# Mircod_TEST_LIST_2.net
KiCad netlist of a schematic drawn in Altium Designer
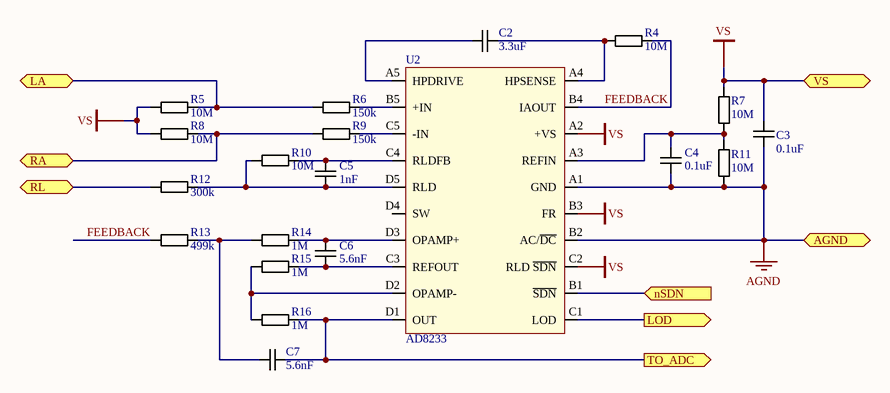
[diagram p0: Mircod_TEST_LIST_2.SchDoc]

(export (version "E")
  (design (tool "Eeschema 10.0.6"))
  (components
    (comp (ref "C2")
      (value "3.3uF")
      (footprint "MIRCOD:Csmd_0402")
      (description "CAPACITOR")
      (libsource (lib "MIRCOD") (part "C_SMD"))
    )
    (comp (ref "C3")
      (value "0.1uF")
      (footprint "MIRCOD:Csmd_0402")
      (description "CAPACITOR")
      (libsource (lib "MIRCOD") (part "C_SMD"))
    )
    (comp (ref "C4")
      (value "0.1uF")
      (footprint "MIRCOD:Csmd_0402")
      (description "CAPACITOR")
      (libsource (lib "MIRCOD") (part "C_SMD"))
    )
    (comp (ref "C5")
      (value "1nF")
      (footprint "MIRCOD:Csmd_0402")
      (description "CAPACITOR")
      (libsource (lib "MIRCOD") (part "C_SMD"))
    )
    (comp (ref "C6")
      (value "5.6nF")
      (footprint "MIRCOD:Csmd_0402")
      (description "CAPACITOR")
      (libsource (lib "MIRCOD") (part "C_SMD"))
    )
    (comp (ref "C7")
      (value "5.6nF")
      (footprint "MIRCOD:Csmd_0402")
      (description "CAPACITOR")
      (libsource (lib "MIRCOD") (part "C_SMD"))
    )
    (comp (ref "R4")
      (value "10M")
      (footprint "MIRCOD:SMD_0402")
      (description "RESISTOR")
      (libsource (lib "MIRCOD") (part "R_SMD"))
    )
    (comp (ref "R5")
      (value "10M")
      (footprint "MIRCOD:SMD_0402")
      (description "RESISTOR")
      (libsource (lib "MIRCOD") (part "R_SMD"))
    )
    (comp (ref "R6")
      (value "150k")
      (footprint "MIRCOD:SMD_0402")
      (description "RESISTOR")
      (libsource (lib "MIRCOD") (part "R_SMD"))
    )
    (comp (ref "R7")
      (value "10M")
      (footprint "MIRCOD:SMD_0402")
      (description "RESISTOR")
      (libsource (lib "MIRCOD") (part "R_SMD"))
    )
    (comp (ref "R8")
      (value "10M")
      (footprint "MIRCOD:SMD_0402")
      (description "RESISTOR")
      (libsource (lib "MIRCOD") (part "R_SMD"))
    )
    (comp (ref "R9")
      (value "150k")
      (footprint "MIRCOD:SMD_0402")
      (description "RESISTOR")
      (libsource (lib "MIRCOD") (part "R_SMD"))
    )
    (comp (ref "R10")
      (value "10M")
      (footprint "MIRCOD:SMD_0402")
      (description "RESISTOR")
      (libsource (lib "MIRCOD") (part "R_SMD"))
    )
    (comp (ref "R11")
      (value "10M")
      (footprint "MIRCOD:SMD_0402")
      (description "RESISTOR")
      (libsource (lib "MIRCOD") (part "R_SMD"))
    )
    (comp (ref "R12")
      (value "300k")
      (footprint "MIRCOD:SMD_0402")
      (description "RESISTOR")
      (libsource (lib "MIRCOD") (part "R_SMD"))
    )
    (comp (ref "R13")
      (value "499k")
      (footprint "MIRCOD:SMD_0402")
      (description "RESISTOR")
      (libsource (lib "MIRCOD") (part "R_SMD"))
    )
    (comp (ref "R14")
      (value "1M")
      (footprint "MIRCOD:SMD_0402")
      (description "RESISTOR")
      (libsource (lib "MIRCOD") (part "R_SMD"))
    )
    (comp (ref "R15")
      (value "1M")
      (footprint "MIRCOD:SMD_0402")
      (description "RESISTOR")
      (libsource (lib "MIRCOD") (part "R_SMD"))
    )
    (comp (ref "R16")
      (value "1M")
      (footprint "MIRCOD:SMD_0402")
      (description "RESISTOR")
      (libsource (lib "MIRCOD") (part "R_SMD"))
    )
    (comp (ref "U2")
      (value "AD8233")
      (footprint "MIRCOD:CB-20-13")
      (description "Low Noise,  Heart Rate Monitor for Wearable Products")
      (libsource (lib "MIRCOD") (part "AD8233"))
    )
  )
  (nets
    (net (code "1") (name "/FEEDBACK") (class "Default")
      (node (ref "R13") (pin "1") (pinfunction "1_1") (pintype "passive"))
      (node (ref "R4") (pin "2") (pinfunction "2_2") (pintype "passive"))
      (node (ref "U2") (pin "B4") (pinfunction "IAOUT_B4") (pintype "passive"))
    )
    (net (code "2") (name "/LA") (class "Default")
      (node (ref "R5") (pin "2") (pinfunction "2_2") (pintype "passive"))
      (node (ref "R6") (pin "1") (pinfunction "1_1") (pintype "passive"))
    )
    (net (code "3") (name "/LOD") (class "Default")
      (node (ref "U2") (pin "C1") (pinfunction "LOD_C1") (pintype "passive"))
    )
    (net (code "4") (name "/RA") (class "Default")
      (node (ref "R8") (pin "2") (pinfunction "2_2") (pintype "passive"))
      (node (ref "R9") (pin "1") (pinfunction "1_1") (pintype "passive"))
    )
    (net (code "5") (name "/RL") (class "Default")
      (node (ref "R12") (pin "1") (pinfunction "1_1") (pintype "passive"))
    )
    (net (code "6") (name "/TO_ADC") (class "Default")
      (node (ref "C7") (pin "1") (pinfunction "1_1") (pintype "passive"))
      (node (ref "R16") (pin "2") (pinfunction "2_2") (pintype "passive"))
      (node (ref "U2") (pin "D1") (pinfunction "OUT_D1") (pintype "passive"))
    )
    (net (code "7") (name "/nSDN") (class "Default")
      (node (ref "U2") (pin "B1") (pinfunction "~{SDN}_B1") (pintype "passive"))
    )
    (net (code "8") (name "AGND") (class "Default")
      (node (ref "C3") (pin "1") (pinfunction "1_1") (pintype "passive"))
      (node (ref "C4") (pin "1") (pinfunction "1_1") (pintype "passive"))
      (node (ref "R11") (pin "1") (pinfunction "1_1") (pintype "passive"))
      (node (ref "U2") (pin "A1") (pinfunction "GND_A1") (pintype "passive"))
      (node (ref "U2") (pin "B2") (pinfunction "AC/~{DC}_B2") (pintype "passive"))
    )
    (net (code "9") (name "Net-(C7-Pad2)") (class "Default")
      (node (ref "C7") (pin "2") (pinfunction "2_2") (pintype "passive"))
      (node (ref "R13") (pin "2") (pinfunction "2_2") (pintype "passive"))
      (node (ref "R14") (pin "1") (pinfunction "1_1") (pintype "passive"))
    )
    (net (code "10") (name "Net-(U2-+IN)") (class "Default")
      (node (ref "R6") (pin "2") (pinfunction "2_2") (pintype "passive"))
      (node (ref "U2") (pin "B5") (pinfunction "+IN_B5") (pintype "passive"))
    )
    (net (code "11") (name "Net-(U2--IN)") (class "Default")
      (node (ref "R9") (pin "2") (pinfunction "2_2") (pintype "passive"))
      (node (ref "U2") (pin "C5") (pinfunction "-IN_C5") (pintype "passive"))
    )
    (net (code "12") (name "Net-(U2-HPDRIVE)") (class "Default")
      (node (ref "C2") (pin "1") (pinfunction "1_1") (pintype "passive"))
      (node (ref "U2") (pin "A5") (pinfunction "HPDRIVE_A5") (pintype "passive"))
    )
    (net (code "13") (name "Net-(U2-HPSENSE)") (class "Default")
      (node (ref "C2") (pin "2") (pinfunction "2_2") (pintype "passive"))
      (node (ref "R4") (pin "1") (pinfunction "1_1") (pintype "passive"))
      (node (ref "U2") (pin "A4") (pinfunction "HPSENSE_A4") (pintype "passive"))
    )
    (net (code "14") (name "Net-(U2-OPAMP+)") (class "Default")
      (node (ref "C6") (pin "2") (pinfunction "2_2") (pintype "passive"))
      (node (ref "R14") (pin "2") (pinfunction "2_2") (pintype "passive"))
      (node (ref "U2") (pin "D3") (pinfunction "OPAMP+_D3") (pintype "passive"))
    )
    (net (code "15") (name "Net-(U2-OPAMP-)") (class "Default")
      (node (ref "R15") (pin "1") (pinfunction "1_1") (pintype "passive"))
      (node (ref "R16") (pin "1") (pinfunction "1_1") (pintype "passive"))
      (node (ref "U2") (pin "D2") (pinfunction "OPAMP-_D2") (pintype "passive"))
    )
    (net (code "16") (name "Net-(U2-REFIN)") (class "Default")
      (node (ref "C4") (pin "2") (pinfunction "2_2") (pintype "passive"))
      (node (ref "R11") (pin "2") (pinfunction "2_2") (pintype "passive"))
      (node (ref "R7") (pin "1") (pinfunction "1_1") (pintype "passive"))
      (node (ref "U2") (pin "A3") (pinfunction "REFIN_A3") (pintype "passive"))
    )
    (net (code "17") (name "Net-(U2-REFOUT)") (class "Default")
      (node (ref "C6") (pin "1") (pinfunction "1_1") (pintype "passive"))
      (node (ref "R15") (pin "2") (pinfunction "2_2") (pintype "passive"))
      (node (ref "U2") (pin "C3") (pinfunction "REFOUT_C3") (pintype "passive"))
    )
    (net (code "18") (name "Net-(U2-RLD)") (class "Default")
      (node (ref "C5") (pin "1") (pinfunction "1_1") (pintype "passive"))
      (node (ref "R10") (pin "1") (pinfunction "1_1") (pintype "passive"))
      (node (ref "R12") (pin "2") (pinfunction "2_2") (pintype "passive"))
      (node (ref "U2") (pin "D5") (pinfunction "RLD_D5") (pintype "passive"))
    )
    (net (code "19") (name "Net-(U2-RLDFB)") (class "Default")
      (node (ref "C5") (pin "2") (pinfunction "2_2") (pintype "passive"))
      (node (ref "R10") (pin "2") (pinfunction "2_2") (pintype "passive"))
      (node (ref "U2") (pin "C4") (pinfunction "RLDFB_C4") (pintype "passive"))
    )
    (net (code "20") (name "VS") (class "Default")
      (node (ref "C3") (pin "2") (pinfunction "2_2") (pintype "passive"))
      (node (ref "R5") (pin "1") (pinfunction "1_1") (pintype "passive"))
      (node (ref "R7") (pin "2") (pinfunction "2_2") (pintype "passive"))
      (node (ref "R8") (pin "1") (pinfunction "1_1") (pintype "passive"))
      (node (ref "U2") (pin "A2") (pinfunction "+VS_A2") (pintype "passive"))
      (node (ref "U2") (pin "B3") (pinfunction "FR_B3") (pintype "passive"))
      (node (ref "U2") (pin "C2") (pinfunction "RLD_~{SDN}_C2") (pintype "passive"))
    )
    (net (code "21") (name "unconnected-(U2-SW-PadD4)") (class "Default")
      (node (ref "U2") (pin "D4") (pinfunction "SW_D4") (pintype "passive"))
    )
  )
)
